# STPedal_STM32.net
KiCad netlist of a schematic drawn in Altium Designer
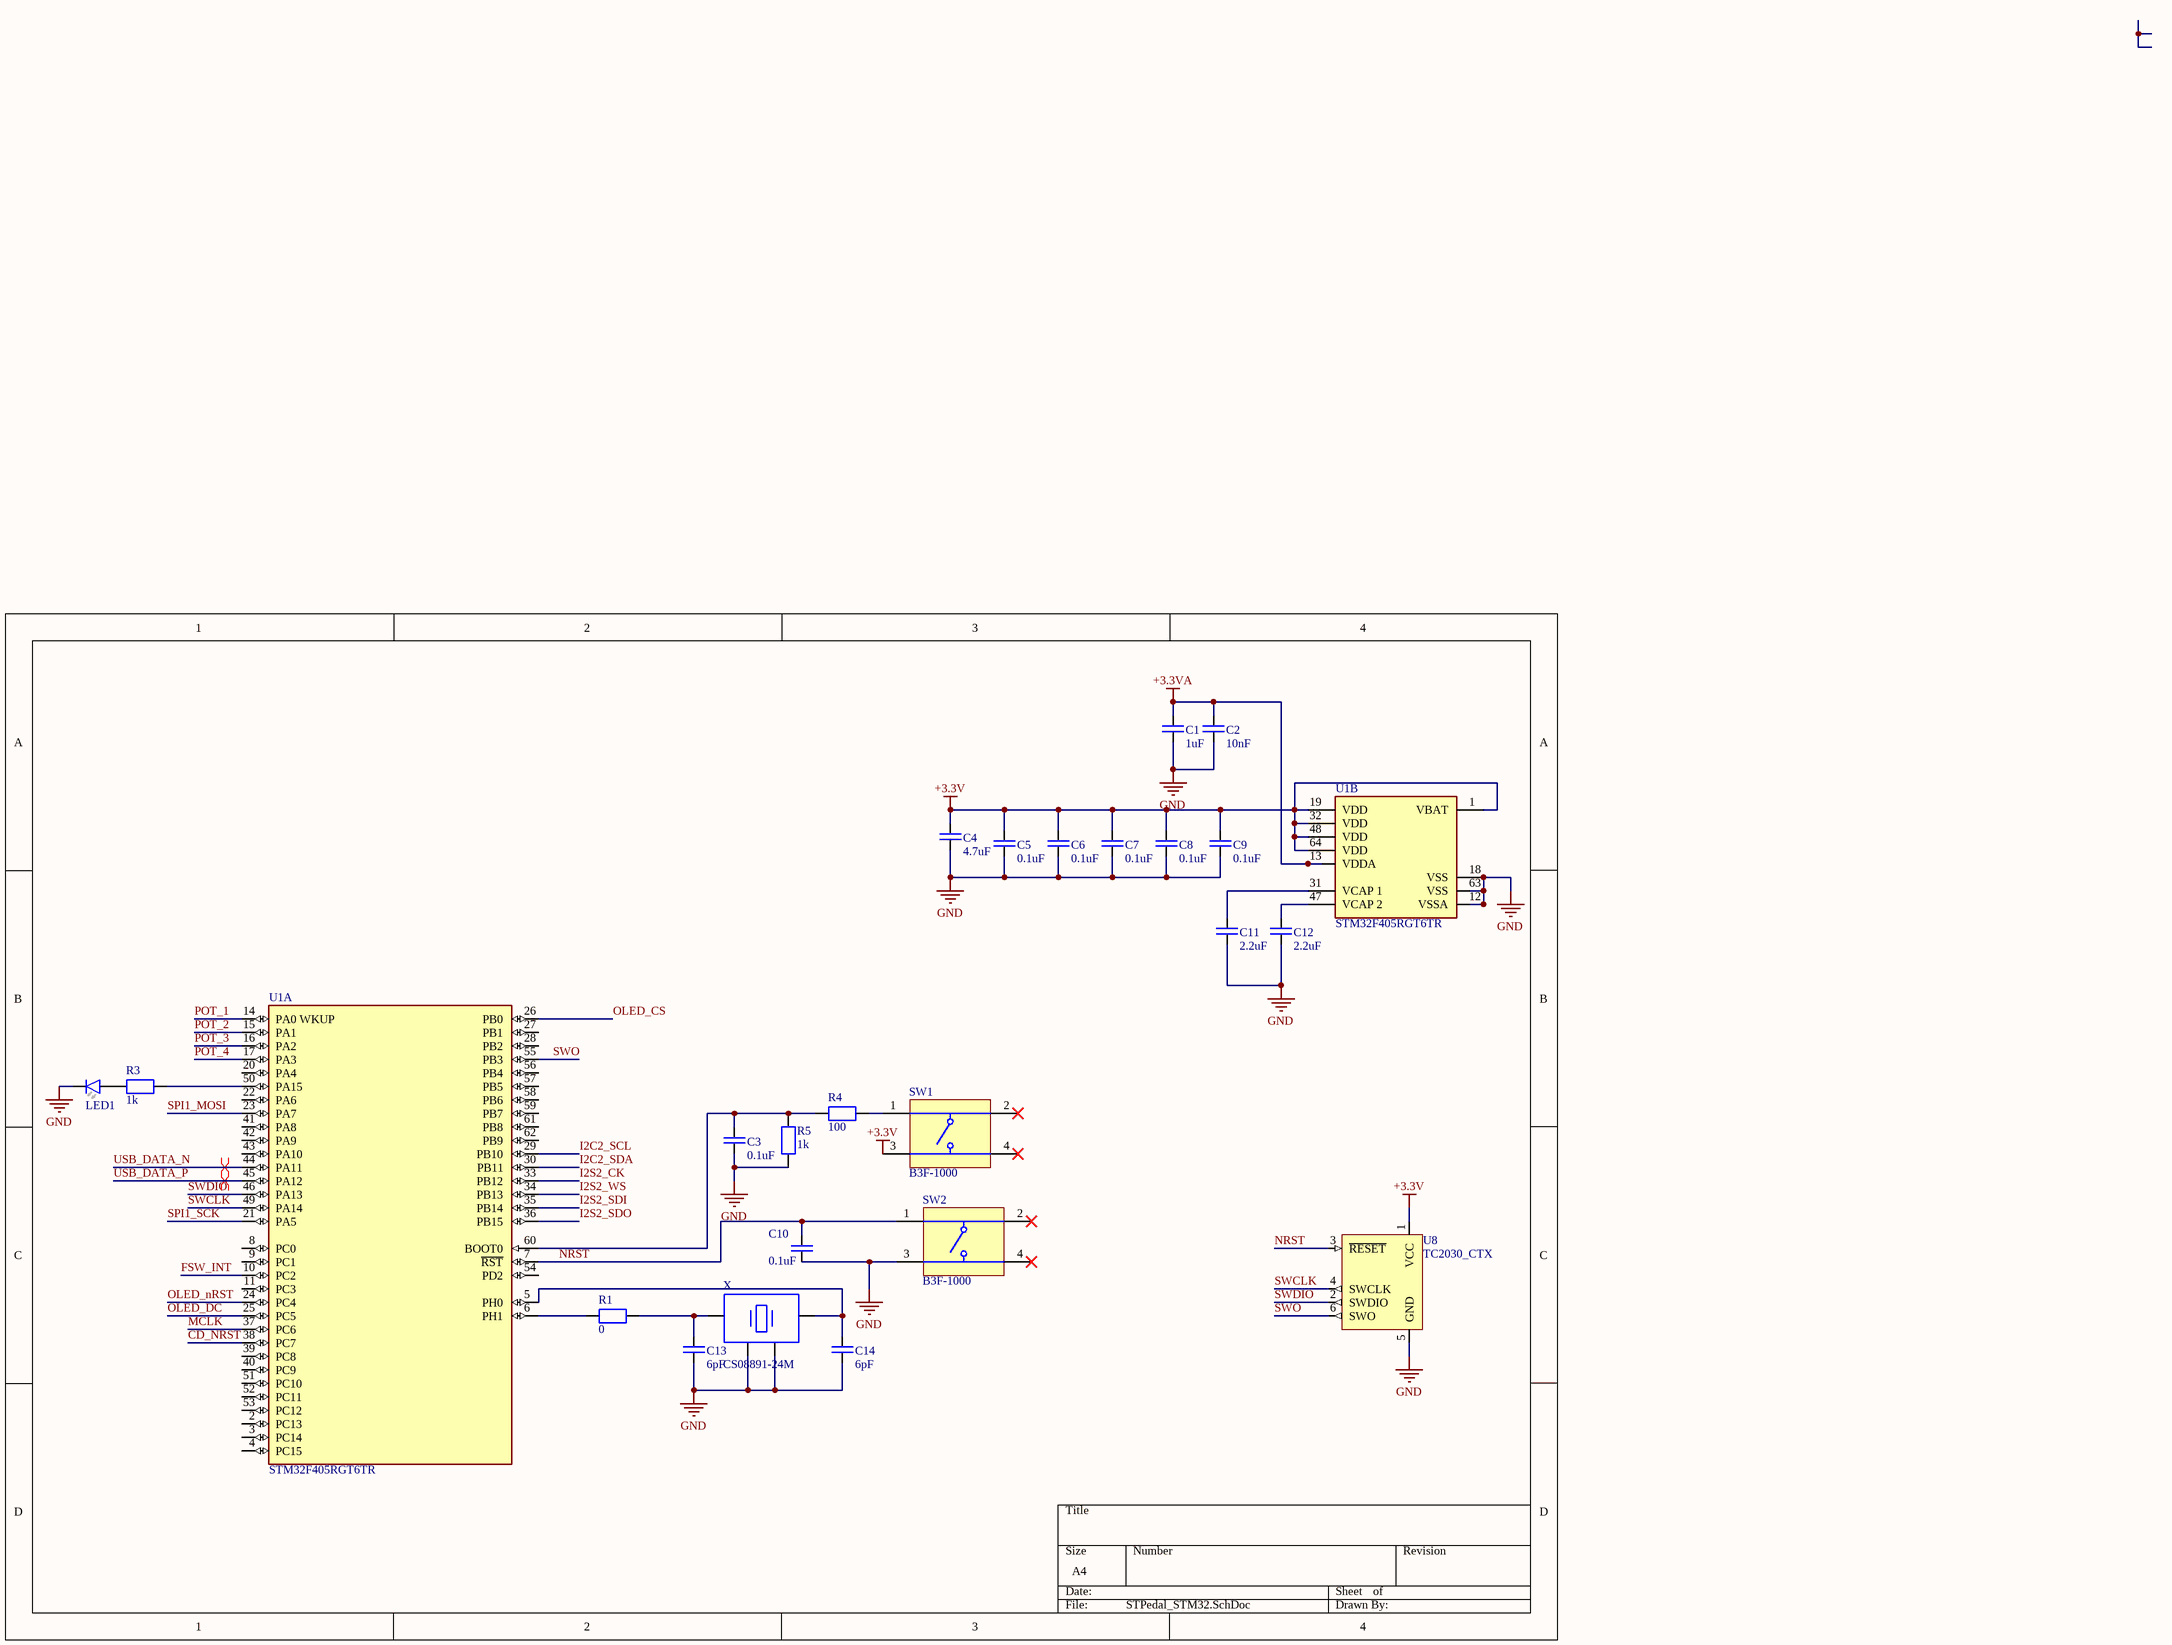
[diagram p0: STPedal_STM32.SchDoc]

(export (version "E")
  (design (tool "Eeschema 10.0.6"))
  (components
    (comp (ref "C1")
      (value "1uF")
      (footprint "CAPC_0402_1005X55N")
      (description "Capacitor 0402 - 1uF +-/10% / 25V")
      (fields
        (field (name "MANUFACTURER") "Samsung Electro-Mechanics")
        (field (name "MPN") "CL05A105KA5NQNC")
      )
      (libsource (lib "ReekoLib") (part "1uF_CAP_0402"))
    )
    (comp (ref "C2")
      (value "10nF")
      (footprint "CAPC_0402_1005X55N")
      (description "Capacitor 0402 - 10nF +-/10% / 25V")
      (fields
        (field (name "MANUFACTURER") "Samsung Electro-Mechanics")
        (field (name "MPN") "CL05B103KB5NNNC")
      )
      (libsource (lib "ReekoLib") (part "10nF_CAP_0402"))
    )
    (comp (ref "C3")
      (value "0.1uF")
      (footprint "CAPC_0402_1005X55N")
      (description "Capacitor 0402 - 0.1uF +-/10% / 16V")
      (fields
        (field (name "MANUFACTURER") "Samsung Electro-Mechanics")
        (field (name "MPN") "CL05B104KO5NNNC")
      )
      (libsource (lib "ReekoLib") (part "0.1uF_CAP_0402"))
    )
    (comp (ref "C4")
      (value "4.7uF")
      (footprint "CAPC_0402_1005X55N")
      (description "Capacitor 0402 - 4.7uF +-/20% / 10V")
      (fields
        (field (name "MANUFACTURER") "Samsung Electro-Mechanics")
        (field (name "MPN") "CL05A475MP5NRNC")
      )
      (libsource (lib "ReekoLib") (part "4.7uF_CAP_0402"))
    )
    (comp (ref "C5")
      (value "0.1uF")
      (footprint "CAPC_0402_1005X55N")
      (description "Capacitor 0402 - 0.1uF +-/10% / 16V")
      (fields
        (field (name "MANUFACTURER") "Samsung Electro-Mechanics")
        (field (name "MPN") "CL05B104KO5NNNC")
      )
      (libsource (lib "ReekoLib") (part "0.1uF_CAP_0402"))
    )
    (comp (ref "C6")
      (value "0.1uF")
      (footprint "CAPC_0402_1005X55N")
      (description "Capacitor 0402 - 0.1uF +-/10% / 16V")
      (fields
        (field (name "MANUFACTURER") "Samsung Electro-Mechanics")
        (field (name "MPN") "CL05B104KO5NNNC")
      )
      (libsource (lib "ReekoLib") (part "0.1uF_CAP_0402"))
    )
    (comp (ref "C7")
      (value "0.1uF")
      (footprint "CAPC_0402_1005X55N")
      (description "Capacitor 0402 - 0.1uF +-/10% / 16V")
      (fields
        (field (name "MANUFACTURER") "Samsung Electro-Mechanics")
        (field (name "MPN") "CL05B104KO5NNNC")
      )
      (libsource (lib "ReekoLib") (part "0.1uF_CAP_0402"))
    )
    (comp (ref "C8")
      (value "0.1uF")
      (footprint "CAPC_0402_1005X55N")
      (description "Capacitor 0402 - 0.1uF +-/10% / 16V")
      (fields
        (field (name "MANUFACTURER") "Samsung Electro-Mechanics")
        (field (name "MPN") "CL05B104KO5NNNC")
      )
      (libsource (lib "ReekoLib") (part "0.1uF_CAP_0402"))
    )
    (comp (ref "C9")
      (value "0.1uF")
      (footprint "CAPC_0402_1005X55N")
      (description "Capacitor 0402 - 0.1uF +-/10% / 16V")
      (fields
        (field (name "MANUFACTURER") "Samsung Electro-Mechanics")
        (field (name "MPN") "CL05B104KO5NNNC")
      )
      (libsource (lib "ReekoLib") (part "0.1uF_CAP_0402"))
    )
    (comp (ref "C10")
      (value "0.1uF")
      (footprint "CAPC_0402_1005X55N")
      (description "Capacitor 0402 - 0.1uF +-/10% / 16V")
      (fields
        (field (name "MANUFACTURER") "Samsung Electro-Mechanics")
        (field (name "MPN") "CL05B104KO5NNNC")
      )
      (libsource (lib "ReekoLib") (part "0.1uF_CAP_0402"))
    )
    (comp (ref "C11")
      (value "2.2uF")
      (footprint "CAPC_0402_1005X55N")
      (description "Capacitor 0402 - 2.2uF +-/10% / 25V")
      (fields
        (field (name "MANUFACTURER") "Samsung Electro-Mechanics")
        (field (name "MPN") "CL05A225MQ5NSNC")
      )
      (libsource (lib "ReekoLib") (part "2.2uF_CAP_0402"))
    )
    (comp (ref "C12")
      (value "2.2uF")
      (footprint "CAPC_0402_1005X55N")
      (description "Capacitor 0402 - 2.2uF +-/10% / 25V")
      (fields
        (field (name "MANUFACTURER") "Samsung Electro-Mechanics")
        (field (name "MPN") "CL05A225MQ5NSNC")
      )
      (libsource (lib "ReekoLib") (part "2.2uF_CAP_0402"))
    )
    (comp (ref "C13")
      (value "6pF")
      (footprint "CAPC_0402_1005X55N")
      (description "Capacitor 0402 - 6pF +-/10% / 50V - C0G")
      (fields
        (field (name "MANUFACTURER") "FH (Guangdong Fenghua Advanced Tech)")
        (field (name "MPN") "0402CG6R0C500NT")
      )
      (libsource (lib "ReekoLib") (part "6pF_CAP_0402"))
    )
    (comp (ref "C14")
      (value "6pF")
      (footprint "CAPC_0402_1005X55N")
      (description "Capacitor 0402 - 6pF +-/10% / 50V - C0G")
      (fields
        (field (name "MANUFACTURER") "FH (Guangdong Fenghua Advanced Tech)")
        (field (name "MPN") "0402CG6R0C500NT")
      )
      (libsource (lib "ReekoLib") (part "6pF_CAP_0402"))
    )
    (comp (ref "LED1")
      (value "LED_White_JLCD_0603")
      (footprint "LED_0603_1608")
      (fields (field (name "MANUFACTURER") "Hubei KENTO Elec") (field (name "MPN") "KT-0603W"))
      (libsource (lib "ReekoLib") (part "LED_White_JLCD_0603"))
    )
    (comp (ref "R1")
      (value "0")
      (footprint "RESC_0402_1005X40N")
      (description "-55℃~+155℃ 0Ω 50V 62.5mW Thick Film Resistor ±1% ±800ppm/℃ 0402 Chip Resistor - Surface Mount ROHS")
      (fields (field (name "MANUFACTURER") "UNI-ROYAL(Uniroyal Elec)") (field (name "MPN") "0402WGF0000TCE"))
      (libsource (lib "ReekoLib") (part "0R_JLCRES-0402"))
    )
    (comp (ref "R3")
      (value "1k")
      (footprint "RESC_0402_1005X40N")
      (description "Resistor 0402 - 1k")
      (fields (field (name "MANUFACTURER") "UNI-ROYAL(Uniroyal Elec)") (field (name "MPN") "0402WGF1001TCE"))
      (libsource (lib "ReekoLib") (part "1k_JLCRES-0402"))
    )
    (comp (ref "R4")
      (value "100")
      (footprint "RESC_0402_1005X40N")
      (description "Resistor 0402 - 100R")
      (libsource (lib "ReekoLib") (part "100R_JLCRES-0402"))
    )
    (comp (ref "R5")
      (value "1k")
      (footprint "RESC_0402_1005X40N")
      (description "Resistor 0402 - 1k")
      (fields (field (name "MANUFACTURER") "UNI-ROYAL(Uniroyal Elec)") (field (name "MPN") "0402WGF1001TCE"))
      (libsource (lib "ReekoLib") (part "1k_JLCRES-0402"))
    )
    (comp (ref "SW1")
      (value "B3F-1000")
      (footprint "OMRON-B3F-1000-4_V")
      (description "Tactile Switch, SPST-NO, 0.05 A, 24 V, -25 to 70 degC, 4-Pin THD, RoHS, Bulk")
      (fields (field (name "MANUFACTURER") "Omron Electronic Components"))
      (libsource (lib "The University of Auckland") (part "SW-SPST-4_A"))
    )
    (comp (ref "SW2")
      (value "B3F-1000")
      (footprint "OMRON-B3F-1000-4_V")
      (description "Tactile Switch, SPST-NO, 0.05 A, 24 V, -25 to 70 degC, 4-Pin THD, RoHS, Bulk")
      (fields (field (name "MANUFACTURER") "Omron Electronic Components"))
      (libsource (lib "The University of Auckland") (part "SW-SPST-4_A"))
    )
    (comp (ref "U1")
      (value "STM32F405RGT6TR")
      (footprint "FP-LQFP64-5W-IPC_C")
      (description "IC MCU 32BIT 1MB FLASH 64LQFP")
      (libsource (lib "Altium Content Vault") (part "179ee1be0515346e2f7079deece093b"))
    )
    (comp (ref "U8")
      (value "TC2030_CTX")
      (footprint "TC2030_CTX")
      (libsource (lib "ReekoLib") (part "TC2030_CTX"))
    )
    (comp (ref "X")
      (value "CS08891-24M")
      (footprint "4 SMD - No Lead")
      (description "CRYSTAL 24.0000MHZ 6PF SMD")
      (libsource (lib "ReekoLib") (part "CS08891-24M"))
    )
  )
  (nets
    (net (code "1") (name "+3.3V") (class "Default")
      (node (ref "C4") (pin "2") (pintype "passive"))
      (node (ref "C5") (pin "2") (pintype "passive"))
      (node (ref "C6") (pin "2") (pintype "passive"))
      (node (ref "C7") (pin "2") (pintype "passive"))
      (node (ref "C8") (pin "2") (pintype "passive"))
      (node (ref "C9") (pin "2") (pintype "passive"))
      (node (ref "SW1") (pin "3") (pinfunction "3_3") (pintype "passive"))
      (node (ref "U1") (pin "1") (pinfunction "VBAT_1") (pintype "power_in"))
      (node (ref "U1") (pin "19") (pinfunction "VDD_19") (pintype "power_in"))
      (node (ref "U1") (pin "32") (pinfunction "VDD_32") (pintype "power_in"))
      (node (ref "U1") (pin "48") (pinfunction "VDD_48") (pintype "power_in"))
      (node (ref "U1") (pin "64") (pinfunction "VDD_64") (pintype "power_in"))
      (node (ref "U8") (pin "1") (pinfunction "VCC_1") (pintype "power_in"))
    )
    (net (code "2") (name "+3.3VA") (class "Default")
      (node (ref "C1") (pin "2") (pintype "passive"))
      (node (ref "C2") (pin "2") (pintype "passive"))
      (node (ref "U1") (pin "13") (pinfunction "VDDA_13") (pintype "power_in"))
    )
    (net (code "3") (name "/CD_NRST") (class "Default")
      (node (ref "U1") (pin "38") (pinfunction "PC7_38") (pintype "bidirectional"))
    )
    (net (code "4") (name "/FSW_INT") (class "Default")
      (node (ref "U1") (pin "10") (pinfunction "PC2_10") (pintype "bidirectional"))
    )
    (net (code "5") (name "/I2C2_SCL") (class "Default")
      (node (ref "U1") (pin "29") (pinfunction "PB10_29") (pintype "bidirectional"))
    )
    (net (code "6") (name "/I2C2_SDA") (class "Default")
      (node (ref "U1") (pin "30") (pinfunction "PB11_30") (pintype "bidirectional"))
    )
    (net (code "7") (name "/I2S2_CK") (class "Default")
      (node (ref "U1") (pin "33") (pinfunction "PB12_33") (pintype "bidirectional"))
    )
    (net (code "8") (name "/I2S2_SDI") (class "Default")
      (node (ref "U1") (pin "35") (pinfunction "PB14_35") (pintype "bidirectional"))
    )
    (net (code "9") (name "/I2S2_SDO") (class "Default")
      (node (ref "U1") (pin "36") (pinfunction "PB15_36") (pintype "bidirectional"))
    )
    (net (code "10") (name "/I2S2_WS") (class "Default")
      (node (ref "U1") (pin "34") (pinfunction "PB13_34") (pintype "bidirectional"))
    )
    (net (code "11") (name "/MCLK") (class "Default")
      (node (ref "U1") (pin "37") (pinfunction "PC6_37") (pintype "bidirectional"))
    )
    (net (code "12") (name "/NRST") (class "Default")
      (node (ref "C10") (pin "2") (pintype "passive"))
      (node (ref "SW2") (pin "1") (pinfunction "1_1") (pintype "passive"))
      (node (ref "U1") (pin "7") (pinfunction "~{RST}_7") (pintype "bidirectional"))
      (node (ref "U8") (pin "3") (pinfunction "~{RESET}_3") (pintype "input"))
    )
    (net (code "13") (name "/OLED_CS") (class "Default")
      (node (ref "U1") (pin "26") (pinfunction "PB0_26") (pintype "bidirectional"))
    )
    (net (code "14") (name "/OLED_DC") (class "Default")
      (node (ref "U1") (pin "25") (pinfunction "PC5_25") (pintype "bidirectional"))
    )
    (net (code "15") (name "/OLED_nRST") (class "Default")
      (node (ref "U1") (pin "24") (pinfunction "PC4_24") (pintype "bidirectional"))
    )
    (net (code "16") (name "/POT_1") (class "Default")
      (node (ref "U1") (pin "14") (pinfunction "PA0_WKUP_14") (pintype "bidirectional"))
    )
    (net (code "17") (name "/POT_2") (class "Default")
      (node (ref "U1") (pin "15") (pinfunction "PA1_15") (pintype "bidirectional"))
    )
    (net (code "18") (name "/POT_3") (class "Default")
      (node (ref "U1") (pin "16") (pinfunction "PA2_16") (pintype "bidirectional"))
    )
    (net (code "19") (name "/POT_4") (class "Default")
      (node (ref "U1") (pin "17") (pinfunction "PA3_17") (pintype "bidirectional"))
    )
    (net (code "20") (name "/SPI1_MOSI") (class "Default")
      (node (ref "U1") (pin "23") (pinfunction "PA7_23") (pintype "bidirectional"))
    )
    (net (code "21") (name "/SPI1_SCK") (class "Default")
      (node (ref "U1") (pin "21") (pinfunction "PA5_21") (pintype "bidirectional"))
    )
    (net (code "22") (name "/SWCLK") (class "Default")
      (node (ref "U1") (pin "49") (pinfunction "PA14_49") (pintype "bidirectional"))
      (node (ref "U8") (pin "4") (pinfunction "SWCLK_4") (pintype "output"))
    )
    (net (code "23") (name "/SWDIO") (class "Default")
      (node (ref "U1") (pin "46") (pinfunction "PA13_46") (pintype "bidirectional"))
      (node (ref "U8") (pin "2") (pinfunction "SWDIO_2") (pintype "output"))
    )
    (net (code "24") (name "/SWO") (class "Default")
      (node (ref "U1") (pin "55") (pinfunction "PB3_55") (pintype "bidirectional"))
      (node (ref "U8") (pin "6") (pinfunction "SWO_6") (pintype "output"))
    )
    (net (code "25") (name "/USB_DATA_N") (class "Default")
      (node (ref "U1") (pin "44") (pinfunction "PA11_44") (pintype "bidirectional"))
    )
    (net (code "26") (name "/USB_DATA_P") (class "Default")
      (node (ref "U1") (pin "45") (pinfunction "PA12_45") (pintype "bidirectional"))
    )
    (net (code "27") (name "GND") (class "Default")
      (node (ref "C1") (pin "1") (pintype "passive"))
      (node (ref "C10") (pin "1") (pintype "passive"))
      (node (ref "C11") (pin "1") (pintype "passive"))
      (node (ref "C12") (pin "1") (pintype "passive"))
      (node (ref "C13") (pin "1") (pintype "passive"))
      (node (ref "C14") (pin "1") (pintype "passive"))
      (node (ref "C2") (pin "1") (pintype "passive"))
      (node (ref "C3") (pin "1") (pintype "passive"))
      (node (ref "C4") (pin "1") (pintype "passive"))
      (node (ref "C5") (pin "1") (pintype "passive"))
      (node (ref "C6") (pin "1") (pintype "passive"))
      (node (ref "C7") (pin "1") (pintype "passive"))
      (node (ref "C8") (pin "1") (pintype "passive"))
      (node (ref "C9") (pin "1") (pintype "passive"))
      (node (ref "LED1") (pin "2") (pintype "passive"))
      (node (ref "R5") (pin "1") (pintype "passive"))
      (node (ref "SW2") (pin "3") (pinfunction "3_3") (pintype "passive"))
      (node (ref "U1") (pin "12") (pinfunction "VSSA_12") (pintype "power_in"))
      (node (ref "U1") (pin "18") (pinfunction "VSS_18") (pintype "power_in"))
      (node (ref "U1") (pin "63") (pinfunction "VSS_63") (pintype "power_in"))
      (node (ref "U8") (pin "5") (pinfunction "GND_5") (pintype "power_in"))
      (node (ref "X") (pin "2") (pintype "power_in"))
      (node (ref "X") (pin "4") (pintype "power_in"))
    )
    (net (code "28") (name "Net-(C13-Pad2)") (class "Default")
      (node (ref "C13") (pin "2") (pintype "passive"))
      (node (ref "R1") (pin "2") (pintype "passive"))
      (node (ref "X") (pin "1") (pintype "passive"))
    )
    (net (code "29") (name "Net-(LED1-Pad1)") (class "Default")
      (node (ref "LED1") (pin "1") (pintype "passive"))
      (node (ref "R3") (pin "1") (pintype "passive"))
    )
    (net (code "30") (name "Net-(R4-Pad2)") (class "Default")
      (node (ref "R4") (pin "2") (pintype "passive"))
      (node (ref "SW1") (pin "1") (pinfunction "1_1") (pintype "passive"))
    )
    (net (code "31") (name "Net-(U1A-BOOT0)") (class "Default")
      (node (ref "C3") (pin "2") (pintype "passive"))
      (node (ref "R4") (pin "1") (pintype "passive"))
      (node (ref "R5") (pin "2") (pintype "passive"))
      (node (ref "U1") (pin "60") (pinfunction "BOOT0_60") (pintype "input"))
    )
    (net (code "32") (name "Net-(U1A-PA15)") (class "Default")
      (node (ref "R3") (pin "2") (pintype "passive"))
      (node (ref "U1") (pin "50") (pinfunction "PA15_50") (pintype "bidirectional"))
    )
    (net (code "33") (name "Net-(U1A-PH0)") (class "Default")
      (node (ref "C14") (pin "2") (pintype "passive"))
      (node (ref "U1") (pin "5") (pinfunction "PH0_5") (pintype "bidirectional"))
      (node (ref "X") (pin "3") (pintype "passive"))
    )
    (net (code "34") (name "Net-(U1A-PH1)") (class "Default")
      (node (ref "R1") (pin "1") (pintype "passive"))
      (node (ref "U1") (pin "6") (pinfunction "PH1_6") (pintype "bidirectional"))
    )
    (net (code "35") (name "Net-(U1B-VCAP_1)") (class "Default")
      (node (ref "C11") (pin "2") (pintype "passive"))
      (node (ref "U1") (pin "31") (pinfunction "VCAP_1_31") (pintype "passive"))
    )
    (net (code "36") (name "Net-(U1B-VCAP_2)") (class "Default")
      (node (ref "C12") (pin "2") (pintype "passive"))
      (node (ref "U1") (pin "47") (pinfunction "VCAP_2_47") (pintype "passive"))
    )
    (net (code "37") (name "unconnected-(SW1-Pad2)") (class "Default")
      (node (ref "SW1") (pin "2") (pinfunction "2_2") (pintype "passive+no_connect"))
    )
    (net (code "38") (name "unconnected-(SW1-Pad4)") (class "Default")
      (node (ref "SW1") (pin "4") (pinfunction "4_4") (pintype "passive+no_connect"))
    )
    (net (code "39") (name "unconnected-(SW2-Pad2)") (class "Default")
      (node (ref "SW2") (pin "2") (pinfunction "2_2") (pintype "passive+no_connect"))
    )
    (net (code "40") (name "unconnected-(SW2-Pad4)") (class "Default")
      (node (ref "SW2") (pin "4") (pinfunction "4_4") (pintype "passive+no_connect"))
    )
    (net (code "41") (name "unconnected-(U1A-PA4-Pad20)") (class "Default")
      (node (ref "U1") (pin "20") (pinfunction "PA4_20") (pintype "bidirectional"))
    )
    (net (code "42") (name "unconnected-(U1A-PA6-Pad22)") (class "Default")
      (node (ref "U1") (pin "22") (pinfunction "PA6_22") (pintype "bidirectional"))
    )
    (net (code "43") (name "unconnected-(U1A-PA8-Pad41)") (class "Default")
      (node (ref "U1") (pin "41") (pinfunction "PA8_41") (pintype "bidirectional"))
    )
    (net (code "44") (name "unconnected-(U1A-PA9-Pad42)") (class "Default")
      (node (ref "U1") (pin "42") (pinfunction "PA9_42") (pintype "bidirectional"))
    )
    (net (code "45") (name "unconnected-(U1A-PA10-Pad43)") (class "Default")
      (node (ref "U1") (pin "43") (pinfunction "PA10_43") (pintype "bidirectional"))
    )
    (net (code "46") (name "unconnected-(U1A-PB1-Pad27)") (class "Default")
      (node (ref "U1") (pin "27") (pinfunction "PB1_27") (pintype "bidirectional"))
    )
    (net (code "47") (name "unconnected-(U1A-PB2-Pad28)") (class "Default")
      (node (ref "U1") (pin "28") (pinfunction "PB2_28") (pintype "bidirectional"))
    )
    (net (code "48") (name "unconnected-(U1A-PB4-Pad56)") (class "Default")
      (node (ref "U1") (pin "56") (pinfunction "PB4_56") (pintype "bidirectional"))
    )
    (net (code "49") (name "unconnected-(U1A-PB5-Pad57)") (class "Default")
      (node (ref "U1") (pin "57") (pinfunction "PB5_57") (pintype "bidirectional"))
    )
    (net (code "50") (name "unconnected-(U1A-PB6-Pad58)") (class "Default")
      (node (ref "U1") (pin "58") (pinfunction "PB6_58") (pintype "bidirectional"))
    )
    (net (code "51") (name "unconnected-(U1A-PB7-Pad59)") (class "Default")
      (node (ref "U1") (pin "59") (pinfunction "PB7_59") (pintype "bidirectional"))
    )
    (net (code "52") (name "unconnected-(U1A-PB8-Pad61)") (class "Default")
      (node (ref "U1") (pin "61") (pinfunction "PB8_61") (pintype "bidirectional"))
    )
    (net (code "53") (name "unconnected-(U1A-PB9-Pad62)") (class "Default")
      (node (ref "U1") (pin "62") (pinfunction "PB9_62") (pintype "bidirectional"))
    )
    (net (code "54") (name "unconnected-(U1A-PC0-Pad8)") (class "Default")
      (node (ref "U1") (pin "8") (pinfunction "PC0_8") (pintype "bidirectional"))
    )
    (net (code "55") (name "unconnected-(U1A-PC1-Pad9)") (class "Default")
      (node (ref "U1") (pin "9") (pinfunction "PC1_9") (pintype "bidirectional"))
    )
    (net (code "56") (name "unconnected-(U1A-PC3-Pad11)") (class "Default")
      (node (ref "U1") (pin "11") (pinfunction "PC3_11") (pintype "bidirectional"))
    )
    (net (code "57") (name "unconnected-(U1A-PC8-Pad39)") (class "Default")
      (node (ref "U1") (pin "39") (pinfunction "PC8_39") (pintype "bidirectional"))
    )
    (net (code "58") (name "unconnected-(U1A-PC9-Pad40)") (class "Default")
      (node (ref "U1") (pin "40") (pinfunction "PC9_40") (pintype "bidirectional"))
    )
    (net (code "59") (name "unconnected-(U1A-PC10-Pad51)") (class "Default")
      (node (ref "U1") (pin "51") (pinfunction "PC10_51") (pintype "bidirectional"))
    )
    (net (code "60") (name "unconnected-(U1A-PC11-Pad52)") (class "Default")
      (node (ref "U1") (pin "52") (pinfunction "PC11_52") (pintype "bidirectional"))
    )
    (net (code "61") (name "unconnected-(U1A-PC12-Pad53)") (class "Default")
      (node (ref "U1") (pin "53") (pinfunction "PC12_53") (pintype "bidirectional"))
    )
    (net (code "62") (name "unconnected-(U1A-PC13-Pad2)") (class "Default")
      (node (ref "U1") (pin "2") (pinfunction "PC13_2") (pintype "bidirectional"))
    )
    (net (code "63") (name "unconnected-(U1A-PC14-Pad3)") (class "Default")
      (node (ref "U1") (pin "3") (pinfunction "PC14_3") (pintype "bidirectional"))
    )
    (net (code "64") (name "unconnected-(U1A-PC15-Pad4)") (class "Default")
      (node (ref "U1") (pin "4") (pinfunction "PC15_4") (pintype "bidirectional"))
    )
    (net (code "65") (name "unconnected-(U1A-PD2-Pad54)") (class "Default")
      (node (ref "U1") (pin "54") (pinfunction "PD2_54") (pintype "bidirectional"))
    )
  )
)
